# power-board.net
KiCad netlist of a schematic drawn in EAGLE
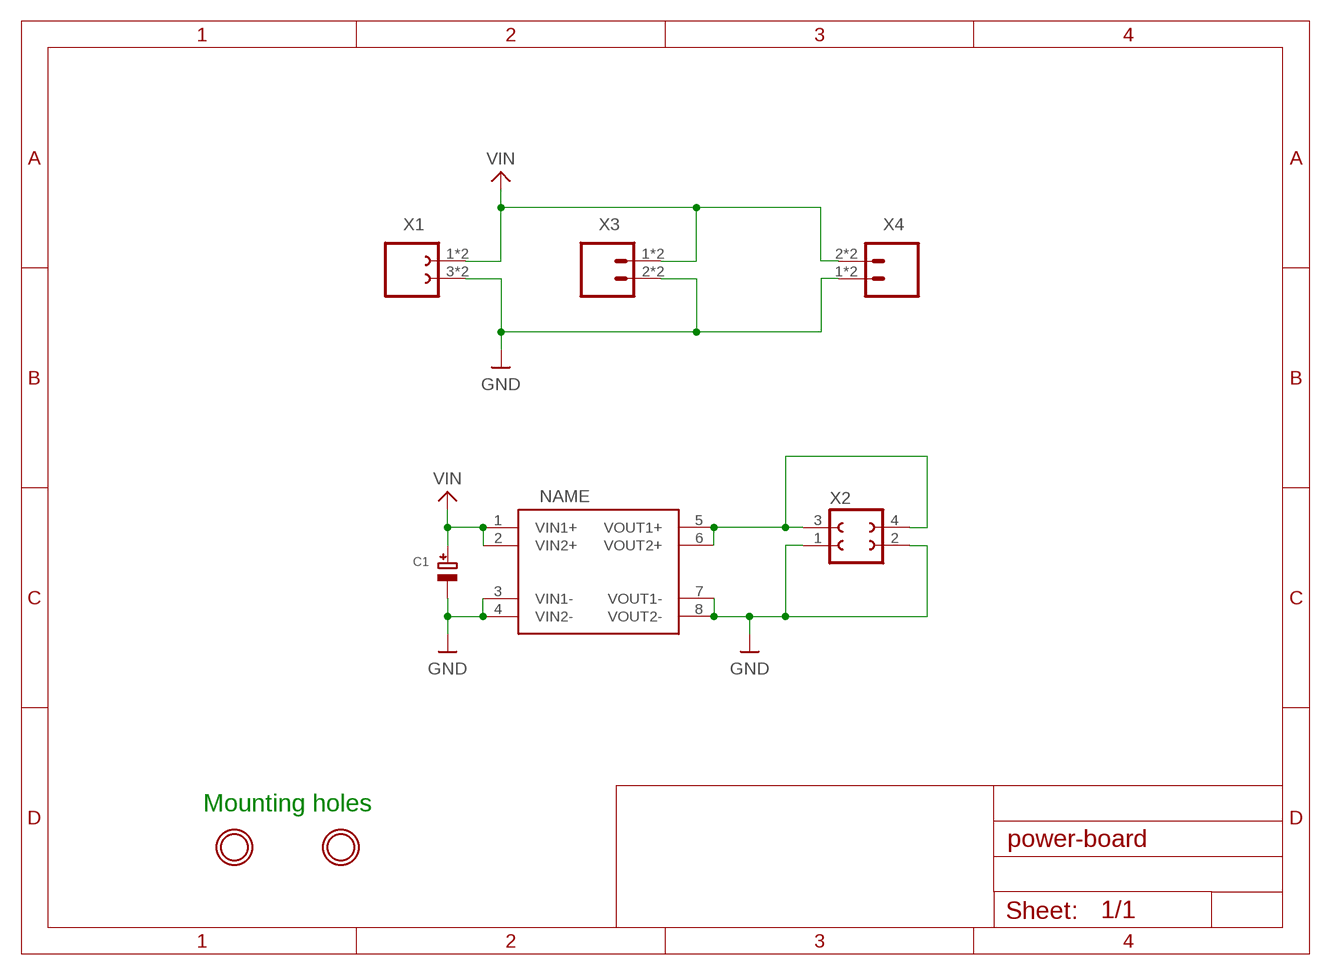
[diagram p0: schematic, sheet 1]

(export (version "E")
  (design (tool "Eeschema 10.0.6"))
  (components
    (comp (ref "C1")
      (value "CAP_ELECTROLYTIC")
      (footprint "eagle-import:CAPPRD350W60D800H800B")
      (libsource (lib "eagle-import") (part "CAP_ELECTROLYTIC"))
    )
    (comp (ref "PS1")
      (value "K8801MODULE")
      (footprint "eagle-import:K8801")
      (libsource (lib "eagle-import") (part "K8801MODULE"))
    )
    (comp (ref "U$2")
      (value "MOUNTINGHOLE2.7_THICK")
      (footprint "eagle-import:MOUNTINGHOLE_2.7_PLATED_THICK")
      (libsource (lib "eagle-import") (part "MOUNTINGHOLE2.7_THICK"))
    )
    (comp (ref "U$3")
      (value "MOUNTINGHOLE2.7_THICK")
      (footprint "eagle-import:MOUNTINGHOLE_2.7_PLATED_THICK")
      (libsource (lib "eagle-import") (part "MOUNTINGHOLE2.7_THICK"))
    )
    (comp (ref "X1")
      (value "CON-FE02-1")
      (footprint "eagle-import:PTSM0,5_2-2,5-HTHRR24")
      (libsource (lib "eagle-import") (part "CON-FE02-1"))
    )
    (comp (ref "X2")
      (value "CON-FE02-2HDRVR4W64P254_2X2")
      (footprint "eagle-import:HDRVR4W64P254_2X2")
      (libsource (lib "eagle-import") (part "CON-FE02-2HDRVR4W64P254_2X2"))
    )
    (comp (ref "X3")
      (value "CON-MA02-1")
      (footprint "eagle-import:AVX-BTB-009159002001106")
      (libsource (lib "eagle-import") (part "CON-MA02-1"))
    )
    (comp (ref "X4")
      (value "CON-MA02-1")
      (footprint "eagle-import:AVX-BTB-009159002001106")
      (libsource (lib "eagle-import") (part "CON-MA02-1"))
    )
  )
  (nets
    (net (code "1") (name "GND") (class "Default")
      (node (ref "C1") (pin "2") (pinfunction "-_2") (pintype "passive"))
      (node (ref "PS1") (pin "3") (pinfunction "VIN1-_3") (pintype "bidirectional"))
      (node (ref "PS1") (pin "4") (pinfunction "VIN2-_4") (pintype "bidirectional"))
      (node (ref "PS1") (pin "7") (pinfunction "VOUT1-_7") (pintype "bidirectional"))
      (node (ref "PS1") (pin "8") (pinfunction "VOUT2-_8") (pintype "bidirectional"))
      (node (ref "X1") (pin "3") (pinfunction "3_3") (pintype "passive"))
      (node (ref "X1") (pin "4") (pinfunction "3_4") (pintype "passive"))
      (node (ref "X2") (pin "1") (pinfunction "1_1") (pintype "passive"))
      (node (ref "X2") (pin "2") (pinfunction "2_2") (pintype "passive"))
      (node (ref "X3") (pin "2") (pinfunction "4_2") (pintype "passive"))
      (node (ref "X3") (pin "4") (pinfunction "4_4") (pintype "passive"))
      (node (ref "X4") (pin "1") (pinfunction "2_1") (pintype "passive"))
      (node (ref "X4") (pin "3") (pinfunction "2_3") (pintype "passive"))
    )
    (net (code "2") (name "Net-(PS1-VOUT1+)") (class "Default")
      (node (ref "PS1") (pin "5") (pinfunction "VOUT1+_5") (pintype "bidirectional"))
      (node (ref "PS1") (pin "6") (pinfunction "VOUT2+_6") (pintype "bidirectional"))
      (node (ref "X2") (pin "3") (pinfunction "3_3") (pintype "passive"))
      (node (ref "X2") (pin "4") (pinfunction "4_4") (pintype "passive"))
    )
    (net (code "3") (name "VIN") (class "Default")
      (node (ref "C1") (pin "1") (pinfunction "+_1") (pintype "passive"))
      (node (ref "PS1") (pin "1") (pinfunction "VIN1+_1") (pintype "bidirectional"))
      (node (ref "PS1") (pin "2") (pinfunction "VIN2+_2") (pintype "bidirectional"))
      (node (ref "X1") (pin "1") (pinfunction "1_1") (pintype "passive"))
      (node (ref "X1") (pin "2") (pinfunction "1_2") (pintype "passive"))
      (node (ref "X3") (pin "1") (pinfunction "2_1") (pintype "passive"))
      (node (ref "X3") (pin "3") (pinfunction "2_3") (pintype "passive"))
      (node (ref "X4") (pin "2") (pinfunction "4_2") (pintype "passive"))
      (node (ref "X4") (pin "4") (pinfunction "4_4") (pintype "passive"))
    )
  )
)
